# 03_-_MICRO_CONTROLLER.net
KiCad netlist of a schematic drawn in Altium Designer
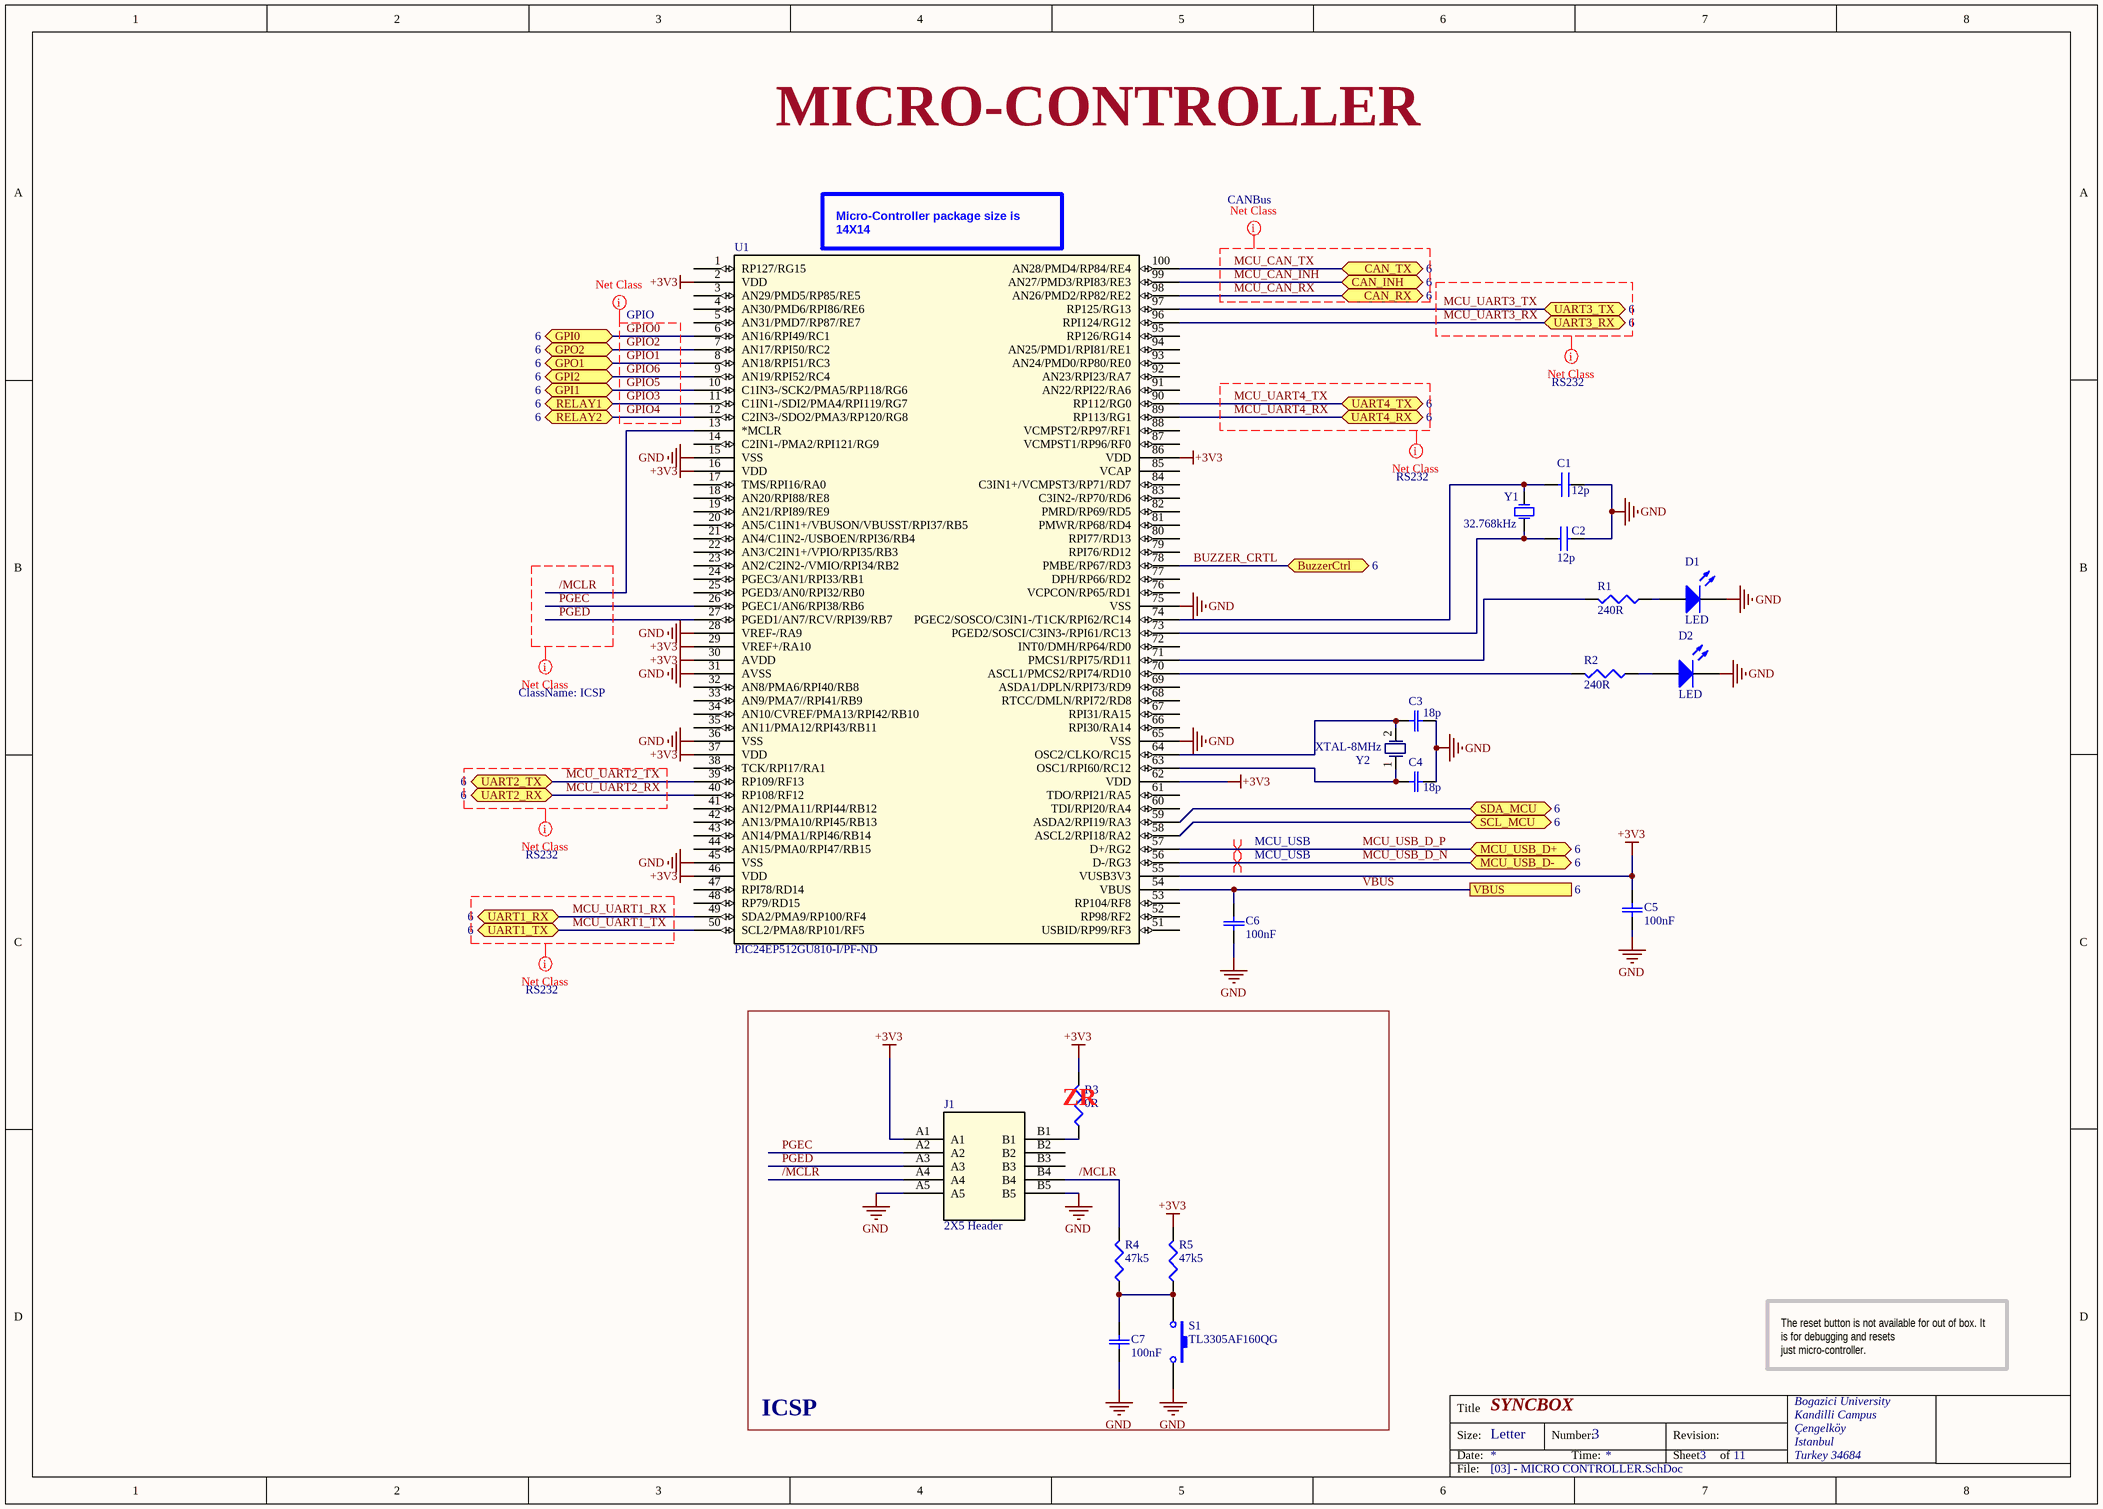
[diagram p0: [03] - MICRO CONTROLLER.SchDoc]

(export (version "E")
  (design (tool "Eeschema 10.0.6"))
  (components
    (comp (ref "C1")
      (value "12p")
      (footprint "C0402")
      (description "CAP CER 12PF 50V C0G 5% 0402")
      (fields (field (name "MANUFACTURER PART NUMBER") "CL05C120JB5NNNC"))
      (libsource (lib "SYNCBOX_V3I1") (part "CL05C120JB5NNNC"))
    )
    (comp (ref "C2")
      (value "12p")
      (footprint "C0402")
      (description "CAP CER 12PF 50V C0G 5% 0402")
      (fields (field (name "MANUFACTURER PART NUMBER") "CL05C120JB5NNNC"))
      (libsource (lib "SYNCBOX_V3I1") (part "CL05C120JB5NNNC"))
    )
    (comp (ref "C3")
      (value "18p")
      (footprint "C0402")
      (description "CAP CER 18PF 50V C0G/NP0 0402")
      (fields (field (name "TOLERANCE") "±5%"))
      (libsource (lib "SYNCBOX_V3I1") (part "CL05C180JB5NNNC"))
    )
    (comp (ref "C4")
      (value "18p")
      (footprint "C0402")
      (description "CAP CER 18PF 50V C0G/NP0 0402")
      (fields (field (name "TOLERANCE") "±5%"))
      (libsource (lib "SYNCBOX_V3I1") (part "CL05C180JB5NNNC"))
    )
    (comp (ref "C5")
      (value "100nF")
      (footprint "C0402")
      (description "CAP CER 0.1UF 50V X8R 0603")
      (fields (field (name "TOLERANCE") "±10%"))
      (libsource (lib "SYNCBOX_V3I1") (part "CL05A104KA5NNNC"))
    )
    (comp (ref "C6")
      (value "100nF")
      (footprint "C0402")
      (description "CAP CER 0.1UF 25V X5R 0402")
      (fields (field (name "TOLERANCE") "±10%") (field (name ".CHECKED SCH") "CHK"))
      (libsource (lib "SYNCBOX_V3I1") (part "CL05A104KA5NNNC"))
    )
    (comp (ref "C7")
      (value "100nF")
      (footprint "C0402")
      (description "CAP CER 0.1UF 50V X8R 0603")
      (fields (field (name "TOLERANCE") "±10%"))
      (libsource (lib "SYNCBOX_V3I1") (part "CL05A104KA5NNNC"))
    )
    (comp (ref "D1")
      (value "LED")
      (footprint "D0603_Directional")
      (description "LED RED DIFFUSED 0603 SMD")
      (fields (field (name "PUBLISHER") "Altium Limited"))
      (libsource (lib "SYNCBOX_V3I1") (part "LS Q976-NR-1"))
    )
    (comp (ref "D2")
      (value "LED")
      (footprint "D0603_Directional")
      (description "LED RED DIFFUSED 0603 SMD")
      (fields (field (name "PUBLISHER") "Altium Limited"))
      (libsource (lib "SYNCBOX_V3I1") (part "LS Q976-NR-1"))
    )
    (comp (ref "J1")
      (value "2X5 Header")
      (footprint "10 Pins")
      (description "CONN HEADER 10POS .100 STR TIN")
      (fields (field (name "MANUFACTURER_PART_NUMBER") "67997-410HLF"))
      (libsource (lib "SYNCBOX_V3I1") (part "67997-410HLF"))
    )
    (comp (ref "R1")
      (value "240R")
      (footprint "R0402")
      (description "RES TF 240 OHM 1% 0.0625W 0402")
      (fields
        (field (name "MANUFACTURER") "Stackpole Electronics Inc")
        (field (name "MANUFACTURER PART NUMBER") "RMCF0402FT240R")
      )
      (libsource (lib "SYNCBOX_V3I1") (part "RMCF0402FT240R"))
    )
    (comp (ref "R2")
      (value "240R")
      (footprint "R0402")
      (description "RES TF 240 OHM 1% 0.0625W 0402")
      (fields
        (field (name "MANUFACTURER") "Stackpole Electronics Inc")
        (field (name "MANUFACTURER PART NUMBER") "RMCF0402FT240R")
      )
      (libsource (lib "SYNCBOX_V3I1") (part "RMCF0402FT240R"))
    )
    (comp (ref "R3")
      (value "0R")
      (footprint "R0402")
      (description "RES SMD 0 OHM JUMPER 1/16W 0402")
      (fields (field (name "TOLERANCE") "Jumper"))
      (libsource (lib "SYNCBOX_V3I1") (part "RC1005J000CS"))
    )
    (comp (ref "R4")
      (value "47k5")
      (footprint "R0402")
      (description "RES 47.5K OHM 1/16W 1% 0402 SMD")
      (fields
        (field (name "MANUFACTURER") "Yageo")
        (field (name "MANUFACTURER PART NUMBER") "RC0402FR-0747K5L")
      )
      (libsource (lib "SYNCBOX_V3I1") (part "RC0402FR-0747K5L"))
    )
    (comp (ref "R5")
      (value "47k5")
      (footprint "R0402")
      (description "RES 47.5K OHM 1/16W 1% 0402 SMD")
      (fields
        (field (name "MANUFACTURER") "Yageo")
        (field (name "MANUFACTURER PART NUMBER") "RC0402FR-0747K5L")
      )
      (libsource (lib "SYNCBOX_V3I1") (part "RC0402FR-0747K5L"))
    )
    (comp (ref "S1")
      (value "TL3305AF160QG")
      (footprint "TactileSW_SMD")
      (description "SWITCH TACTILE SPST-NO 50MA 12V")
      (libsource (lib "SYNCBOX_V3I1") (part "TL3305AF160QG"))
    )
    (comp (ref "U1")
      (value "PIC24EP512GU810-I/PF-ND")
      (footprint "TQFP100_14x14MC")
      (description "IC MCU 16BIT 512KB FLASH 100TQFP")
      (fields
        (field (name "MANUFACTURER_PART_NUMBER") "PIC24EP512GU810-I/PT")
        (field (name "BASE PART NUMBER") "PIC24EP512GU810")
      )
      (libsource (lib "SYNCBOX_V3I1") (part "PIC24EP512GU810-"))
    )
    (comp (ref "Y1")
      (value "32.768kHz")
      (footprint "XTAL-1.1mm")
      (description "32768 Hz RTC Crystal")
      (fields (field (name "MANUFACTURER PART NUMBER") "AB38T-32.768KHZ"))
      (libsource (lib "SYNCBOX_V3I1") (part "XTAL_32.768kHz"))
    )
    (comp (ref "Y2")
      (value "XTAL-8MHz")
      (footprint "HC49/US")
      (description "8MHz ±30ppm Crystal 18pF 80 Ohm -20°C ~ 70°C  Surface Mount HC49/US")
      (fields (field (name "TOLERANCE") "30 PPM"))
      (libsource (lib "SYNCBOX_V3I1") (part "Crystal-8MHz"))
    )
  )
  (nets
    (net (code "1") (name "+3V3") (class "Default")
      (node (ref "C5") (pin "2") (pinfunction "2_2") (pintype "passive"))
      (node (ref "J1") (pin "A1") (pinfunction "A1_A1") (pintype "passive"))
      (node (ref "R3") (pin "2") (pinfunction "2_2") (pintype "passive"))
      (node (ref "R5") (pin "2") (pinfunction "2_2") (pintype "passive"))
      (node (ref "U1") (pin "16") (pinfunction "VDD_16") (pintype "passive"))
      (node (ref "U1") (pin "2") (pinfunction "VDD_2") (pintype "passive"))
      (node (ref "U1") (pin "29") (pinfunction "VREF+/RA10_29") (pintype "passive"))
      (node (ref "U1") (pin "30") (pinfunction "AVDD_30") (pintype "passive"))
      (node (ref "U1") (pin "37") (pinfunction "VDD_37") (pintype "passive"))
      (node (ref "U1") (pin "46") (pinfunction "VDD_46") (pintype "passive"))
      (node (ref "U1") (pin "55") (pinfunction "VUSB3V3_55") (pintype "passive"))
      (node (ref "U1") (pin "62") (pinfunction "VDD_62") (pintype "passive"))
      (node (ref "U1") (pin "86") (pinfunction "VDD_86") (pintype "passive"))
    )
    (net (code "2") (name "/BUZZER_CRTL") (class "Default")
      (node (ref "U1") (pin "78") (pinfunction "PMBE/RP67/RD3_78") (pintype "bidirectional"))
    )
    (net (code "3") (name "/GPIO0") (class "Default")
      (node (ref "U1") (pin "6") (pinfunction "AN16/RPI49/RC1_6") (pintype "bidirectional"))
    )
    (net (code "4") (name "/GPIO1") (class "Default")
      (node (ref "U1") (pin "8") (pinfunction "AN18/RPI51/RC3_8") (pintype "bidirectional"))
    )
    (net (code "5") (name "/GPIO2") (class "Default")
      (node (ref "U1") (pin "7") (pinfunction "AN17/RPI50/RC2_7") (pintype "bidirectional"))
    )
    (net (code "6") (name "/GPIO3") (class "Default")
      (node (ref "U1") (pin "11") (pinfunction "C1IN1-/SDI2/PMA4/RPI119/RG7_11") (pintype "bidirectional"))
    )
    (net (code "7") (name "/GPIO4") (class "Default")
      (node (ref "U1") (pin "12") (pinfunction "C2IN3-/SDO2/PMA3/RP120/RG8_12") (pintype "bidirectional"))
    )
    (net (code "8") (name "/GPIO5") (class "Default")
      (node (ref "U1") (pin "10") (pinfunction "C1IN3-/SCK2/PMA5/RP118/RG6_10") (pintype "bidirectional"))
    )
    (net (code "9") (name "/GPIO6") (class "Default")
      (node (ref "U1") (pin "9") (pinfunction "AN19/RPI52/RC4_9") (pintype "bidirectional"))
    )
    (net (code "10") (name "/MCU_CAN_INH") (class "Default")
      (node (ref "U1") (pin "99") (pinfunction "AN27/PMD3/RPI83/RE3_99") (pintype "bidirectional"))
    )
    (net (code "11") (name "/MCU_CAN_RX") (class "Default")
      (node (ref "U1") (pin "98") (pinfunction "AN26/PMD2/RP82/RE2_98") (pintype "bidirectional"))
    )
    (net (code "12") (name "/MCU_CAN_TX") (class "Default")
      (node (ref "U1") (pin "100") (pinfunction "AN28/PMD4/RP84/RE4_100") (pintype "bidirectional"))
    )
    (net (code "13") (name "/MCU_UART1_RX") (class "Default")
      (node (ref "U1") (pin "49") (pinfunction "SDA2/PMA9/RP100/RF4_49") (pintype "bidirectional"))
    )
    (net (code "14") (name "/MCU_UART1_TX") (class "Default")
      (node (ref "U1") (pin "50") (pinfunction "SCL2/PMA8/RP101/RF5_50") (pintype "bidirectional"))
    )
    (net (code "15") (name "/MCU_UART2_RX") (class "Default")
      (node (ref "U1") (pin "40") (pinfunction "RP108/RF12_40") (pintype "bidirectional"))
    )
    (net (code "16") (name "/MCU_UART2_TX") (class "Default")
      (node (ref "U1") (pin "39") (pinfunction "RP109/RF13_39") (pintype "bidirectional"))
    )
    (net (code "17") (name "/MCU_UART3_RX") (class "Default")
      (node (ref "U1") (pin "96") (pinfunction "RPI124/RG12_96") (pintype "bidirectional"))
    )
    (net (code "18") (name "/MCU_UART3_TX") (class "Default")
      (node (ref "U1") (pin "97") (pinfunction "RP125/RG13_97") (pintype "bidirectional"))
    )
    (net (code "19") (name "/MCU_UART4_RX") (class "Default")
      (node (ref "U1") (pin "89") (pinfunction "RP113/RG1_89") (pintype "bidirectional"))
    )
    (net (code "20") (name "/MCU_UART4_TX") (class "Default")
      (node (ref "U1") (pin "90") (pinfunction "RP112/RG0_90") (pintype "bidirectional"))
    )
    (net (code "21") (name "/MCU_USB_D_N") (class "Default")
      (node (ref "U1") (pin "56") (pinfunction "D-/RG3_56") (pintype "bidirectional"))
    )
    (net (code "22") (name "/MCU_USB_D_P") (class "Default")
      (node (ref "U1") (pin "57") (pinfunction "D+/RG2_57") (pintype "bidirectional"))
    )
    (net (code "23") (name "/PGEC") (class "Default")
      (node (ref "J1") (pin "A2") (pinfunction "A2_A2") (pintype "passive"))
      (node (ref "U1") (pin "26") (pinfunction "PGEC1/AN6/RPI38/RB6_26") (pintype "bidirectional"))
    )
    (net (code "24") (name "/PGED") (class "Default")
      (node (ref "J1") (pin "A3") (pinfunction "A3_A3") (pintype "passive"))
      (node (ref "U1") (pin "27") (pinfunction "PGED1/AN7/RCV/RPI39/RB7_27") (pintype "bidirectional"))
    )
    (net (code "25") (name "/SCL_MCU") (class "Default")
      (node (ref "U1") (pin "58") (pinfunction "ASCL2/RPI18/RA2_58") (pintype "bidirectional"))
    )
    (net (code "26") (name "/SDA_MCU") (class "Default")
      (node (ref "U1") (pin "59") (pinfunction "ASDA2/RPI19/RA3_59") (pintype "bidirectional"))
    )
    (net (code "27") (name "/VBUS") (class "Default")
      (node (ref "C6") (pin "2") (pinfunction "2_2") (pintype "passive"))
      (node (ref "U1") (pin "54") (pinfunction "VBUS_54") (pintype "passive"))
    )
    (net (code "28") (name "/{slash}MCLR") (class "Default")
      (node (ref "J1") (pin "A4") (pinfunction "A4_A4") (pintype "passive"))
      (node (ref "J1") (pin "B4") (pinfunction "B4_B4") (pintype "passive"))
      (node (ref "R4") (pin "2") (pinfunction "2_2") (pintype "passive"))
      (node (ref "U1") (pin "13") (pinfunction "*MCLR_13") (pintype "passive"))
    )
    (net (code "29") (name "GND") (class "Default")
      (node (ref "C1") (pin "1") (pinfunction "1_1") (pintype "passive"))
      (node (ref "C2") (pin "2") (pinfunction "2_2") (pintype "passive"))
      (node (ref "C3") (pin "1") (pinfunction "1_1") (pintype "passive"))
      (node (ref "C4") (pin "1") (pinfunction "1_1") (pintype "passive"))
      (node (ref "C5") (pin "1") (pinfunction "1_1") (pintype "passive"))
      (node (ref "C6") (pin "1") (pinfunction "1_1") (pintype "passive"))
      (node (ref "C7") (pin "1") (pinfunction "1_1") (pintype "passive"))
      (node (ref "D1") (pin "2") (pinfunction "K_2") (pintype "passive"))
      (node (ref "D2") (pin "2") (pinfunction "K_2") (pintype "passive"))
      (node (ref "J1") (pin "A5") (pinfunction "A5_A5") (pintype "passive"))
      (node (ref "J1") (pin "B5") (pinfunction "B5_B5") (pintype "passive"))
      (node (ref "S1") (pin "2") (pinfunction "2_2") (pintype "passive"))
      (node (ref "U1") (pin "15") (pinfunction "VSS_15") (pintype "passive"))
      (node (ref "U1") (pin "28") (pinfunction "VREF-/RA9_28") (pintype "passive"))
      (node (ref "U1") (pin "31") (pinfunction "AVSS_31") (pintype "passive"))
      (node (ref "U1") (pin "36") (pinfunction "VSS_36") (pintype "passive"))
      (node (ref "U1") (pin "45") (pinfunction "VSS_45") (pintype "passive"))
      (node (ref "U1") (pin "65") (pinfunction "VSS_65") (pintype "passive"))
      (node (ref "U1") (pin "75") (pinfunction "VSS_75") (pintype "passive"))
    )
    (net (code "30") (name "Net-(C7-Pad2)") (class "Default")
      (node (ref "C7") (pin "2") (pinfunction "2_2") (pintype "passive"))
      (node (ref "R4") (pin "1") (pinfunction "1_1") (pintype "passive"))
      (node (ref "R5") (pin "1") (pinfunction "1_1") (pintype "passive"))
      (node (ref "S1") (pin "1") (pinfunction "1_1") (pintype "passive"))
    )
    (net (code "31") (name "Net-(D1-A)") (class "Default")
      (node (ref "D1") (pin "1") (pinfunction "A_1") (pintype "passive"))
      (node (ref "R1") (pin "1") (pinfunction "1_1") (pintype "passive"))
    )
    (net (code "32") (name "Net-(D2-A)") (class "Default")
      (node (ref "D2") (pin "1") (pinfunction "A_1") (pintype "passive"))
      (node (ref "R2") (pin "1") (pinfunction "1_1") (pintype "passive"))
    )
    (net (code "33") (name "Net-(J1-PadB1)") (class "Default")
      (node (ref "J1") (pin "B1") (pinfunction "B1_B1") (pintype "passive"))
      (node (ref "R3") (pin "1") (pinfunction "1_1") (pintype "passive"))
    )
    (net (code "34") (name "Net-(U1-ASCL1{slash}PMCS2{slash}RPI74{slash}RD10)") (class "Default")
      (node (ref "R2") (pin "2") (pinfunction "2_2") (pintype "passive"))
      (node (ref "U1") (pin "70") (pinfunction "ASCL1/PMCS2/RPI74/RD10_70") (pintype "bidirectional"))
    )
    (net (code "35") (name "Net-(U1-OSC1{slash}RPI60{slash}RC12)") (class "Default")
      (node (ref "C4") (pin "2") (pinfunction "2_2") (pintype "passive"))
      (node (ref "U1") (pin "63") (pinfunction "OSC1/RPI60/RC12_63") (pintype "bidirectional"))
      (node (ref "Y2") (pin "1") (pinfunction "1_1") (pintype "passive"))
    )
    (net (code "36") (name "Net-(U1-OSC2{slash}CLKO{slash}RC15)") (class "Default")
      (node (ref "C3") (pin "2") (pinfunction "2_2") (pintype "passive"))
      (node (ref "U1") (pin "64") (pinfunction "OSC2/CLKO/RC15_64") (pintype "bidirectional"))
      (node (ref "Y2") (pin "2") (pinfunction "2_2") (pintype "passive"))
    )
    (net (code "37") (name "Net-(U1-PGEC2{slash}SOSCO{slash}C3IN1-{slash}T1CK{slash}RPI62{slash}RC14)") (class "Default")
      (node (ref "C1") (pin "2") (pinfunction "2_2") (pintype "passive"))
      (node (ref "U1") (pin "74") (pinfunction "PGEC2/SOSCO/C3IN1-/T1CK/RPI62/RC14_74") (pintype "bidirectional"))
      (node (ref "Y1") (pin "2") (pinfunction "OSC2_2") (pintype "passive"))
    )
    (net (code "38") (name "Net-(U1-PGED2{slash}SOSCI{slash}C3IN3-{slash}RPI61{slash}RC13)") (class "Default")
      (node (ref "C2") (pin "1") (pinfunction "1_1") (pintype "passive"))
      (node (ref "U1") (pin "73") (pinfunction "PGED2/SOSCI/C3IN3-/RPI61/RC13_73") (pintype "bidirectional"))
      (node (ref "Y1") (pin "1") (pinfunction "OSC1_1") (pintype "passive"))
    )
    (net (code "39") (name "Net-(U1-PMCS1{slash}RPI75{slash}RD11)") (class "Default")
      (node (ref "R1") (pin "2") (pinfunction "2_2") (pintype "passive"))
      (node (ref "U1") (pin "71") (pinfunction "PMCS1/RPI75/RD11_71") (pintype "bidirectional"))
    )
    (net (code "40") (name "unconnected-(J1-PadB2)") (class "Default")
      (node (ref "J1") (pin "B2") (pinfunction "B2_B2") (pintype "passive"))
    )
    (net (code "41") (name "unconnected-(J1-PadB3)") (class "Default")
      (node (ref "J1") (pin "B3") (pinfunction "B3_B3") (pintype "passive"))
    )
    (net (code "42") (name "unconnected-(U1-AN2{slash}C2IN2-{slash}VMIO{slash}RPI34{slash}RB2-Pad23)") (class "Default")
      (node (ref "U1") (pin "23") (pinfunction "AN2/C2IN2-/VMIO/RPI34/RB2_23") (pintype "bidirectional"))
    )
    (net (code "43") (name "unconnected-(U1-AN3{slash}C2IN1+{slash}VPIO{slash}RPI35{slash}RB3-Pad22)") (class "Default")
      (node (ref "U1") (pin "22") (pinfunction "AN3/C2IN1+/VPIO/RPI35/RB3_22") (pintype "bidirectional"))
    )
    (net (code "44") (name "unconnected-(U1-AN4{slash}C1IN2-{slash}USBOEN{slash}RPI36{slash}RB4-Pad21)") (class "Default")
      (node (ref "U1") (pin "21") (pinfunction "AN4/C1IN2-/USBOEN/RPI36/RB4_21") (pintype "bidirectional"))
    )
    (net (code "45") (name "unconnected-(U1-AN5{slash}C1IN1+{slash}VBUSON{slash}VBUSST{slash}RPI37{slash}RB5-Pad20)") (class "Default")
      (node (ref "U1") (pin "20") (pinfunction "AN5/C1IN1+/VBUSON/VBUSST/RPI37/RB5_20") (pintype "bidirectional"))
    )
    (net (code "46") (name "unconnected-(U1-AN8{slash}PMA6{slash}RPI40{slash}RB8-Pad32)") (class "Default")
      (node (ref "U1") (pin "32") (pinfunction "AN8/PMA6/RPI40/RB8_32") (pintype "bidirectional"))
    )
    (net (code "47") (name "unconnected-(U1-AN9{slash}PMA7{slash}{slash}RPI41{slash}RB9-Pad33)") (class "Default")
      (node (ref "U1") (pin "33") (pinfunction "AN9/PMA7//RPI41/RB9_33") (pintype "bidirectional"))
    )
    (net (code "48") (name "unconnected-(U1-AN10{slash}CVREF{slash}PMA13{slash}RPI42{slash}RB10-Pad34)") (class "Default")
      (node (ref "U1") (pin "34") (pinfunction "AN10/CVREF/PMA13/RPI42/RB10_34") (pintype "bidirectional"))
    )
    (net (code "49") (name "unconnected-(U1-AN11{slash}PMA12{slash}RPI43{slash}RB11-Pad35)") (class "Default")
      (node (ref "U1") (pin "35") (pinfunction "AN11/PMA12/RPI43/RB11_35") (pintype "bidirectional"))
    )
    (net (code "50") (name "unconnected-(U1-AN12{slash}PMA11{slash}RPI44{slash}RB12-Pad41)") (class "Default")
      (node (ref "U1") (pin "41") (pinfunction "AN12/PMA11/RPI44/RB12_41") (pintype "bidirectional"))
    )
    (net (code "51") (name "unconnected-(U1-AN13{slash}PMA10{slash}RPI45{slash}RB13-Pad42)") (class "Default")
      (node (ref "U1") (pin "42") (pinfunction "AN13/PMA10/RPI45/RB13_42") (pintype "bidirectional"))
    )
    (net (code "52") (name "unconnected-(U1-AN14{slash}PMA1{slash}RPI46{slash}RB14-Pad43)") (class "Default")
      (node (ref "U1") (pin "43") (pinfunction "AN14/PMA1/RPI46/RB14_43") (pintype "bidirectional"))
    )
    (net (code "53") (name "unconnected-(U1-AN15{slash}PMA0{slash}RPI47{slash}RB15-Pad44)") (class "Default")
      (node (ref "U1") (pin "44") (pinfunction "AN15/PMA0/RPI47/RB15_44") (pintype "bidirectional"))
    )
    (net (code "54") (name "unconnected-(U1-AN20{slash}RPI88{slash}RE8-Pad18)") (class "Default")
      (node (ref "U1") (pin "18") (pinfunction "AN20/RPI88/RE8_18") (pintype "bidirectional"))
    )
    (net (code "55") (name "unconnected-(U1-AN21{slash}RPI89{slash}RE9-Pad19)") (class "Default")
      (node (ref "U1") (pin "19") (pinfunction "AN21/RPI89/RE9_19") (pintype "bidirectional"))
    )
    (net (code "56") (name "unconnected-(U1-AN22{slash}RPI22{slash}RA6-Pad91)") (class "Default")
      (node (ref "U1") (pin "91") (pinfunction "AN22/RPI22/RA6_91") (pintype "bidirectional"))
    )
    (net (code "57") (name "unconnected-(U1-AN23{slash}RPI23{slash}RA7-Pad92)") (class "Default")
      (node (ref "U1") (pin "92") (pinfunction "AN23/RPI23/RA7_92") (pintype "bidirectional"))
    )
    (net (code "58") (name "unconnected-(U1-AN24{slash}PMD0{slash}RP80{slash}RE0-Pad93)") (class "Default")
      (node (ref "U1") (pin "93") (pinfunction "AN24/PMD0/RP80/RE0_93") (pintype "bidirectional"))
    )
    (net (code "59") (name "unconnected-(U1-AN25{slash}PMD1{slash}RPI81{slash}RE1-Pad94)") (class "Default")
      (node (ref "U1") (pin "94") (pinfunction "AN25/PMD1/RPI81/RE1_94") (pintype "bidirectional"))
    )
    (net (code "60") (name "unconnected-(U1-AN29{slash}PMD5{slash}RP85{slash}RE5-Pad3)") (class "Default")
      (node (ref "U1") (pin "3") (pinfunction "AN29/PMD5/RP85/RE5_3") (pintype "bidirectional"))
    )
    (net (code "61") (name "unconnected-(U1-AN30{slash}PMD6{slash}RPI86{slash}RE6-Pad4)") (class "Default")
      (node (ref "U1") (pin "4") (pinfunction "AN30/PMD6/RPI86/RE6_4") (pintype "bidirectional"))
    )
    (net (code "62") (name "unconnected-(U1-AN31{slash}PMD7{slash}RP87{slash}RE7-Pad5)") (class "Default")
      (node (ref "U1") (pin "5") (pinfunction "AN31/PMD7/RP87/RE7_5") (pintype "bidirectional"))
    )
    (net (code "63") (name "unconnected-(U1-ASDA1{slash}DPLN{slash}RPI73{slash}RD9-Pad69)") (class "Default")
      (node (ref "U1") (pin "69") (pinfunction "ASDA1/DPLN/RPI73/RD9_69") (pintype "bidirectional"))
    )
    (net (code "64") (name "unconnected-(U1-C2IN1-{slash}PMA2{slash}RPI121{slash}RG9-Pad14)") (class "Default")
      (node (ref "U1") (pin "14") (pinfunction "C2IN1-/PMA2/RPI121/RG9_14") (pintype "bidirectional"))
    )
    (net (code "65") (name "unconnected-(U1-C3IN1+{slash}VCMPST3{slash}RP71{slash}RD7-Pad84)") (class "Default")
      (node (ref "U1") (pin "84") (pinfunction "C3IN1+/VCMPST3/RP71/RD7_84") (pintype "bidirectional"))
    )
    (net (code "66") (name "unconnected-(U1-C3IN2-{slash}RP70{slash}RD6-Pad83)") (class "Default")
      (node (ref "U1") (pin "83") (pinfunction "C3IN2-/RP70/RD6_83") (pintype "bidirectional"))
    )
    (net (code "67") (name "unconnected-(U1-DPH{slash}RP66{slash}RD2-Pad77)") (class "Default")
      (node (ref "U1") (pin "77") (pinfunction "DPH/RP66/RD2_77") (pintype "bidirectional"))
    )
    (net (code "68") (name "unconnected-(U1-INT0{slash}DMH{slash}RP64{slash}RD0-Pad72)") (class "Default")
      (node (ref "U1") (pin "72") (pinfunction "INT0/DMH/RP64/RD0_72") (pintype "bidirectional"))
    )
    (net (code "69") (name "unconnected-(U1-PGEC3{slash}AN1{slash}RPI33{slash}RB1-Pad24)") (class "Default")
      (node (ref "U1") (pin "24") (pinfunction "PGEC3/AN1/RPI33/RB1_24") (pintype "bidirectional"))
    )
    (net (code "70") (name "unconnected-(U1-PGED3{slash}AN0{slash}RPI32{slash}RB0-Pad25)") (class "Default")
      (node (ref "U1") (pin "25") (pinfunction "PGED3/AN0/RPI32/RB0_25") (pintype "bidirectional"))
    )
    (net (code "71") (name "unconnected-(U1-PMRD{slash}RP69{slash}RD5-Pad82)") (class "Default")
      (node (ref "U1") (pin "82") (pinfunction "PMRD/RP69/RD5_82") (pintype "bidirectional"))
    )
    (net (code "72") (name "unconnected-(U1-PMWR{slash}RP68{slash}RD4-Pad81)") (class "Default")
      (node (ref "U1") (pin "81") (pinfunction "PMWR/RP68/RD4_81") (pintype "bidirectional"))
    )
    (net (code "73") (name "unconnected-(U1-RP79{slash}RD15-Pad48)") (class "Default")
      (node (ref "U1") (pin "48") (pinfunction "RP79/RD15_48") (pintype "bidirectional"))
    )
    (net (code "74") (name "unconnected-(U1-RP98{slash}RF2-Pad52)") (class "Default")
      (node (ref "U1") (pin "52") (pinfunction "RP98/RF2_52") (pintype "bidirectional"))
    )
    (net (code "75") (name "unconnected-(U1-RP104{slash}RF8-Pad53)") (class "Default")
      (node (ref "U1") (pin "53") (pinfunction "RP104/RF8_53") (pintype "bidirectional"))
    )
    (net (code "76") (name "unconnected-(U1-RP126{slash}RG14-Pad95)") (class "Default")
      (node (ref "U1") (pin "95") (pinfunction "RP126/RG14_95") (pintype "bidirectional"))
    )
    (net (code "77") (name "unconnected-(U1-RP127{slash}RG15-Pad1)") (class "Default")
      (node (ref "U1") (pin "1") (pinfunction "RP127/RG15_1") (pintype "bidirectional"))
    )
    (net (code "78") (name "unconnected-(U1-RPI30{slash}RA14-Pad66)") (class "Default")
      (node (ref "U1") (pin "66") (pinfunction "RPI30/RA14_66") (pintype "bidirectional"))
    )
    (net (code "79") (name "unconnected-(U1-RPI31{slash}RA15-Pad67)") (class "Default")
      (node (ref "U1") (pin "67") (pinfunction "RPI31/RA15_67") (pintype "bidirectional"))
    )
    (net (code "80") (name "unconnected-(U1-RPI76{slash}RD12-Pad79)") (class "Default")
      (node (ref "U1") (pin "79") (pinfunction "RPI76/RD12_79") (pintype "bidirectional"))
    )
    (net (code "81") (name "unconnected-(U1-RPI77{slash}RD13-Pad80)") (class "Default")
      (node (ref "U1") (pin "80") (pinfunction "RPI77/RD13_80") (pintype "bidirectional"))
    )
    (net (code "82") (name "unconnected-(U1-RPI78{slash}RD14-Pad47)") (class "Default")
      (node (ref "U1") (pin "47") (pinfunction "RPI78/RD14_47") (pintype "bidirectional"))
    )
    (net (code "83") (name "unconnected-(U1-RTCC{slash}DMLN{slash}RPI72{slash}RD8-Pad68)") (class "Default")
      (node (ref "U1") (pin "68") (pinfunction "RTCC/DMLN/RPI72/RD8_68") (pintype "bidirectional"))
    )
    (net (code "84") (name "unconnected-(U1-TCK{slash}RPI17{slash}RA1-Pad38)") (class "Default")
      (node (ref "U1") (pin "38") (pinfunction "TCK/RPI17/RA1_38") (pintype "bidirectional"))
    )
    (net (code "85") (name "unconnected-(U1-TDI{slash}RPI20{slash}RA4-Pad60)") (class "Default")
      (node (ref "U1") (pin "60") (pinfunction "TDI/RPI20/RA4_60") (pintype "bidirectional"))
    )
    (net (code "86") (name "unconnected-(U1-TDO{slash}RPI21{slash}RA5-Pad61)") (class "Default")
      (node (ref "U1") (pin "61") (pinfunction "TDO/RPI21/RA5_61") (pintype "bidirectional"))
    )
    (net (code "87") (name "unconnected-(U1-TMS{slash}RPI16{slash}RA0-Pad17)") (class "Default")
      (node (ref "U1") (pin "17") (pinfunction "TMS/RPI16/RA0_17") (pintype "bidirectional"))
    )
    (net (code "88") (name "unconnected-(U1-USBID{slash}RP99{slash}RF3-Pad51)") (class "Default")
      (node (ref "U1") (pin "51") (pinfunction "USBID/RP99/RF3_51") (pintype "bidirectional"))
    )
    (net (code "89") (name "unconnected-(U1-VCAP-Pad85)") (class "Default")
      (node (ref "U1") (pin "85") (pinfunction "VCAP_85") (pintype "passive"))
    )
    (net (code "90") (name "unconnected-(U1-VCMPST1{slash}RP96{slash}RF0-Pad87)") (class "Default")
      (node (ref "U1") (pin "87") (pinfunction "VCMPST1/RP96/RF0_87") (pintype "bidirectional"))
    )
    (net (code "91") (name "unconnected-(U1-VCMPST2{slash}RP97{slash}RF1-Pad88)") (class "Default")
      (node (ref "U1") (pin "88") (pinfunction "VCMPST2/RP97/RF1_88") (pintype "bidirectional"))
    )
    (net (code "92") (name "unconnected-(U1-VCPCON{slash}RP65{slash}RD1-Pad76)") (class "Default")
      (node (ref "U1") (pin "76") (pinfunction "VCPCON/RP65/RD1_76") (pintype "bidirectional"))
    )
  )
)
